# PLACAInterconexion.net
KiCad netlist of a schematic drawn in Altium Designer
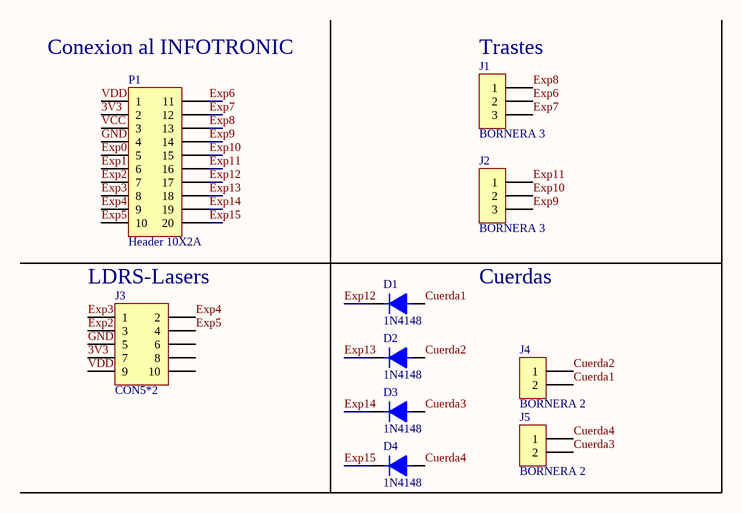
[diagram p0: PLACAInterconexion.SchDoc]

(export (version "E")
  (design (tool "Eeschema 10.0.6"))
  (components
    (comp (ref "D1") (value "1N4148") (footprint "DO41") (libsource (lib "LibGorra") (part "DIODO")))
    (comp (ref "D2") (value "1N4148") (footprint "DO41") (libsource (lib "LibGorra") (part "DIODO")))
    (comp (ref "D3") (value "1N4148") (footprint "DO41") (libsource (lib "LibGorra") (part "DIODO")))
    (comp (ref "D4") (value "1N4148") (footprint "DO41") (libsource (lib "LibGorra") (part "DIODO")))
    (comp (ref "J1")
      (value "BORNERA 3")
      (footprint "BORNERA3")
      (libsource (lib "LIBEBAL") (part "BORNERA 3"))
    )
    (comp (ref "J2")
      (value "BORNERA 3")
      (footprint "BORNERA3")
      (libsource (lib "LIBEBAL") (part "BORNERA 3"))
    )
    (comp (ref "J3") (value "CON5*2") (footprint "SIP5*2") (libsource (lib "LIBEBAL") (part "CON5*2")))
    (comp (ref "J4")
      (value "BORNERA 2")
      (footprint "BORNERA2")
      (libsource (lib "LIBEBAL") (part "BORNERA 2"))
    )
    (comp (ref "J5")
      (value "BORNERA 2")
      (footprint "BORNERA2")
      (libsource (lib "LIBEBAL") (part "BORNERA 2"))
    )
    (comp (ref "P1")
      (value "Header 10X2A")
      (footprint "HDR2X10_CEN")
      (description "Header, 10-Pin, Dual row")
      (fields (field (name "PUBLISHER") "Altium Limited"))
      (libsource (lib "Miscellaneous Connectors") (part "Header 10X2A"))
    )
  )
  (nets
    (net (code "1") (name "/3V3") (class "Default")
      (node (ref "J3") (pin "7") (pinfunction "7_7") (pintype "passive"))
      (node (ref "P1") (pin "2") (pinfunction "2_2") (pintype "passive"))
    )
    (net (code "2") (name "/Cuerda1") (class "Default")
      (node (ref "D1") (pin "1") (pinfunction "1_1") (pintype "passive"))
      (node (ref "J4") (pin "2") (pinfunction "2_2") (pintype "passive"))
    )
    (net (code "3") (name "/Cuerda2") (class "Default")
      (node (ref "D2") (pin "1") (pinfunction "1_1") (pintype "passive"))
      (node (ref "J4") (pin "1") (pinfunction "1_1") (pintype "passive"))
    )
    (net (code "4") (name "/Cuerda3") (class "Default")
      (node (ref "D3") (pin "1") (pinfunction "1_1") (pintype "passive"))
      (node (ref "J5") (pin "2") (pinfunction "2_2") (pintype "passive"))
    )
    (net (code "5") (name "/Cuerda4") (class "Default")
      (node (ref "D4") (pin "1") (pinfunction "1_1") (pintype "passive"))
      (node (ref "J5") (pin "1") (pinfunction "1_1") (pintype "passive"))
    )
    (net (code "6") (name "/Exp0") (class "Default")
      (node (ref "P1") (pin "5") (pinfunction "5_5") (pintype "passive"))
    )
    (net (code "7") (name "/Exp1") (class "Default")
      (node (ref "P1") (pin "6") (pinfunction "6_6") (pintype "passive"))
    )
    (net (code "8") (name "/Exp2") (class "Default")
      (node (ref "J3") (pin "3") (pinfunction "3_3") (pintype "passive"))
      (node (ref "P1") (pin "7") (pinfunction "7_7") (pintype "passive"))
    )
    (net (code "9") (name "/Exp3") (class "Default")
      (node (ref "J3") (pin "1") (pinfunction "1_1") (pintype "passive"))
      (node (ref "P1") (pin "8") (pinfunction "8_8") (pintype "passive"))
    )
    (net (code "10") (name "/Exp4") (class "Default")
      (node (ref "J3") (pin "2") (pinfunction "2_2") (pintype "passive"))
      (node (ref "P1") (pin "9") (pinfunction "9_9") (pintype "passive"))
    )
    (net (code "11") (name "/Exp5") (class "Default")
      (node (ref "J3") (pin "4") (pinfunction "4_4") (pintype "passive"))
      (node (ref "P1") (pin "10") (pinfunction "10_10") (pintype "passive"))
    )
    (net (code "12") (name "/Exp6") (class "Default")
      (node (ref "J1") (pin "2") (pinfunction "2_2") (pintype "passive"))
      (node (ref "P1") (pin "11") (pinfunction "11_11") (pintype "passive"))
    )
    (net (code "13") (name "/Exp7") (class "Default")
      (node (ref "J1") (pin "3") (pinfunction "3_3") (pintype "passive"))
      (node (ref "P1") (pin "12") (pinfunction "12_12") (pintype "passive"))
    )
    (net (code "14") (name "/Exp8") (class "Default")
      (node (ref "J1") (pin "1") (pinfunction "1_1") (pintype "passive"))
      (node (ref "P1") (pin "13") (pinfunction "13_13") (pintype "passive"))
    )
    (net (code "15") (name "/Exp9") (class "Default")
      (node (ref "J2") (pin "3") (pinfunction "3_3") (pintype "passive"))
      (node (ref "P1") (pin "14") (pinfunction "14_14") (pintype "passive"))
    )
    (net (code "16") (name "/Exp10") (class "Default")
      (node (ref "J2") (pin "2") (pinfunction "2_2") (pintype "passive"))
      (node (ref "P1") (pin "15") (pinfunction "15_15") (pintype "passive"))
    )
    (net (code "17") (name "/Exp11") (class "Default")
      (node (ref "J2") (pin "1") (pinfunction "1_1") (pintype "passive"))
      (node (ref "P1") (pin "16") (pinfunction "16_16") (pintype "passive"))
    )
    (net (code "18") (name "/Exp12") (class "Default")
      (node (ref "D1") (pin "2") (pinfunction "2_2") (pintype "passive"))
      (node (ref "P1") (pin "17") (pinfunction "17_17") (pintype "passive"))
    )
    (net (code "19") (name "/Exp13") (class "Default")
      (node (ref "D2") (pin "2") (pinfunction "2_2") (pintype "passive"))
      (node (ref "P1") (pin "18") (pinfunction "18_18") (pintype "passive"))
    )
    (net (code "20") (name "/Exp14") (class "Default")
      (node (ref "D3") (pin "2") (pinfunction "2_2") (pintype "passive"))
      (node (ref "P1") (pin "19") (pinfunction "19_19") (pintype "passive"))
    )
    (net (code "21") (name "/Exp15") (class "Default")
      (node (ref "D4") (pin "2") (pinfunction "2_2") (pintype "passive"))
      (node (ref "P1") (pin "20") (pinfunction "20_20") (pintype "passive"))
    )
    (net (code "22") (name "/GND") (class "Default")
      (node (ref "J3") (pin "5") (pinfunction "5_5") (pintype "passive"))
      (node (ref "P1") (pin "4") (pinfunction "4_4") (pintype "passive"))
    )
    (net (code "23") (name "/VCC") (class "Default")
      (node (ref "P1") (pin "3") (pinfunction "3_3") (pintype "passive"))
    )
    (net (code "24") (name "/VDD") (class "Default")
      (node (ref "J3") (pin "9") (pinfunction "9_9") (pintype "passive"))
      (node (ref "P1") (pin "1") (pinfunction "1_1") (pintype "passive"))
    )
    (net (code "25") (name "unconnected-(J3-Pad6)") (class "Default")
      (node (ref "J3") (pin "6") (pinfunction "6_6") (pintype "passive"))
    )
    (net (code "26") (name "unconnected-(J3-Pad8)") (class "Default")
      (node (ref "J3") (pin "8") (pinfunction "8_8") (pintype "passive"))
    )
    (net (code "27") (name "unconnected-(J3-Pad10)") (class "Default")
      (node (ref "J3") (pin "10") (pinfunction "10_10") (pintype "passive"))
    )
  )
)
